# NV08C_GPS_shield_v1_1_reduced.net
KiCad netlist of a schematic drawn in EAGLE
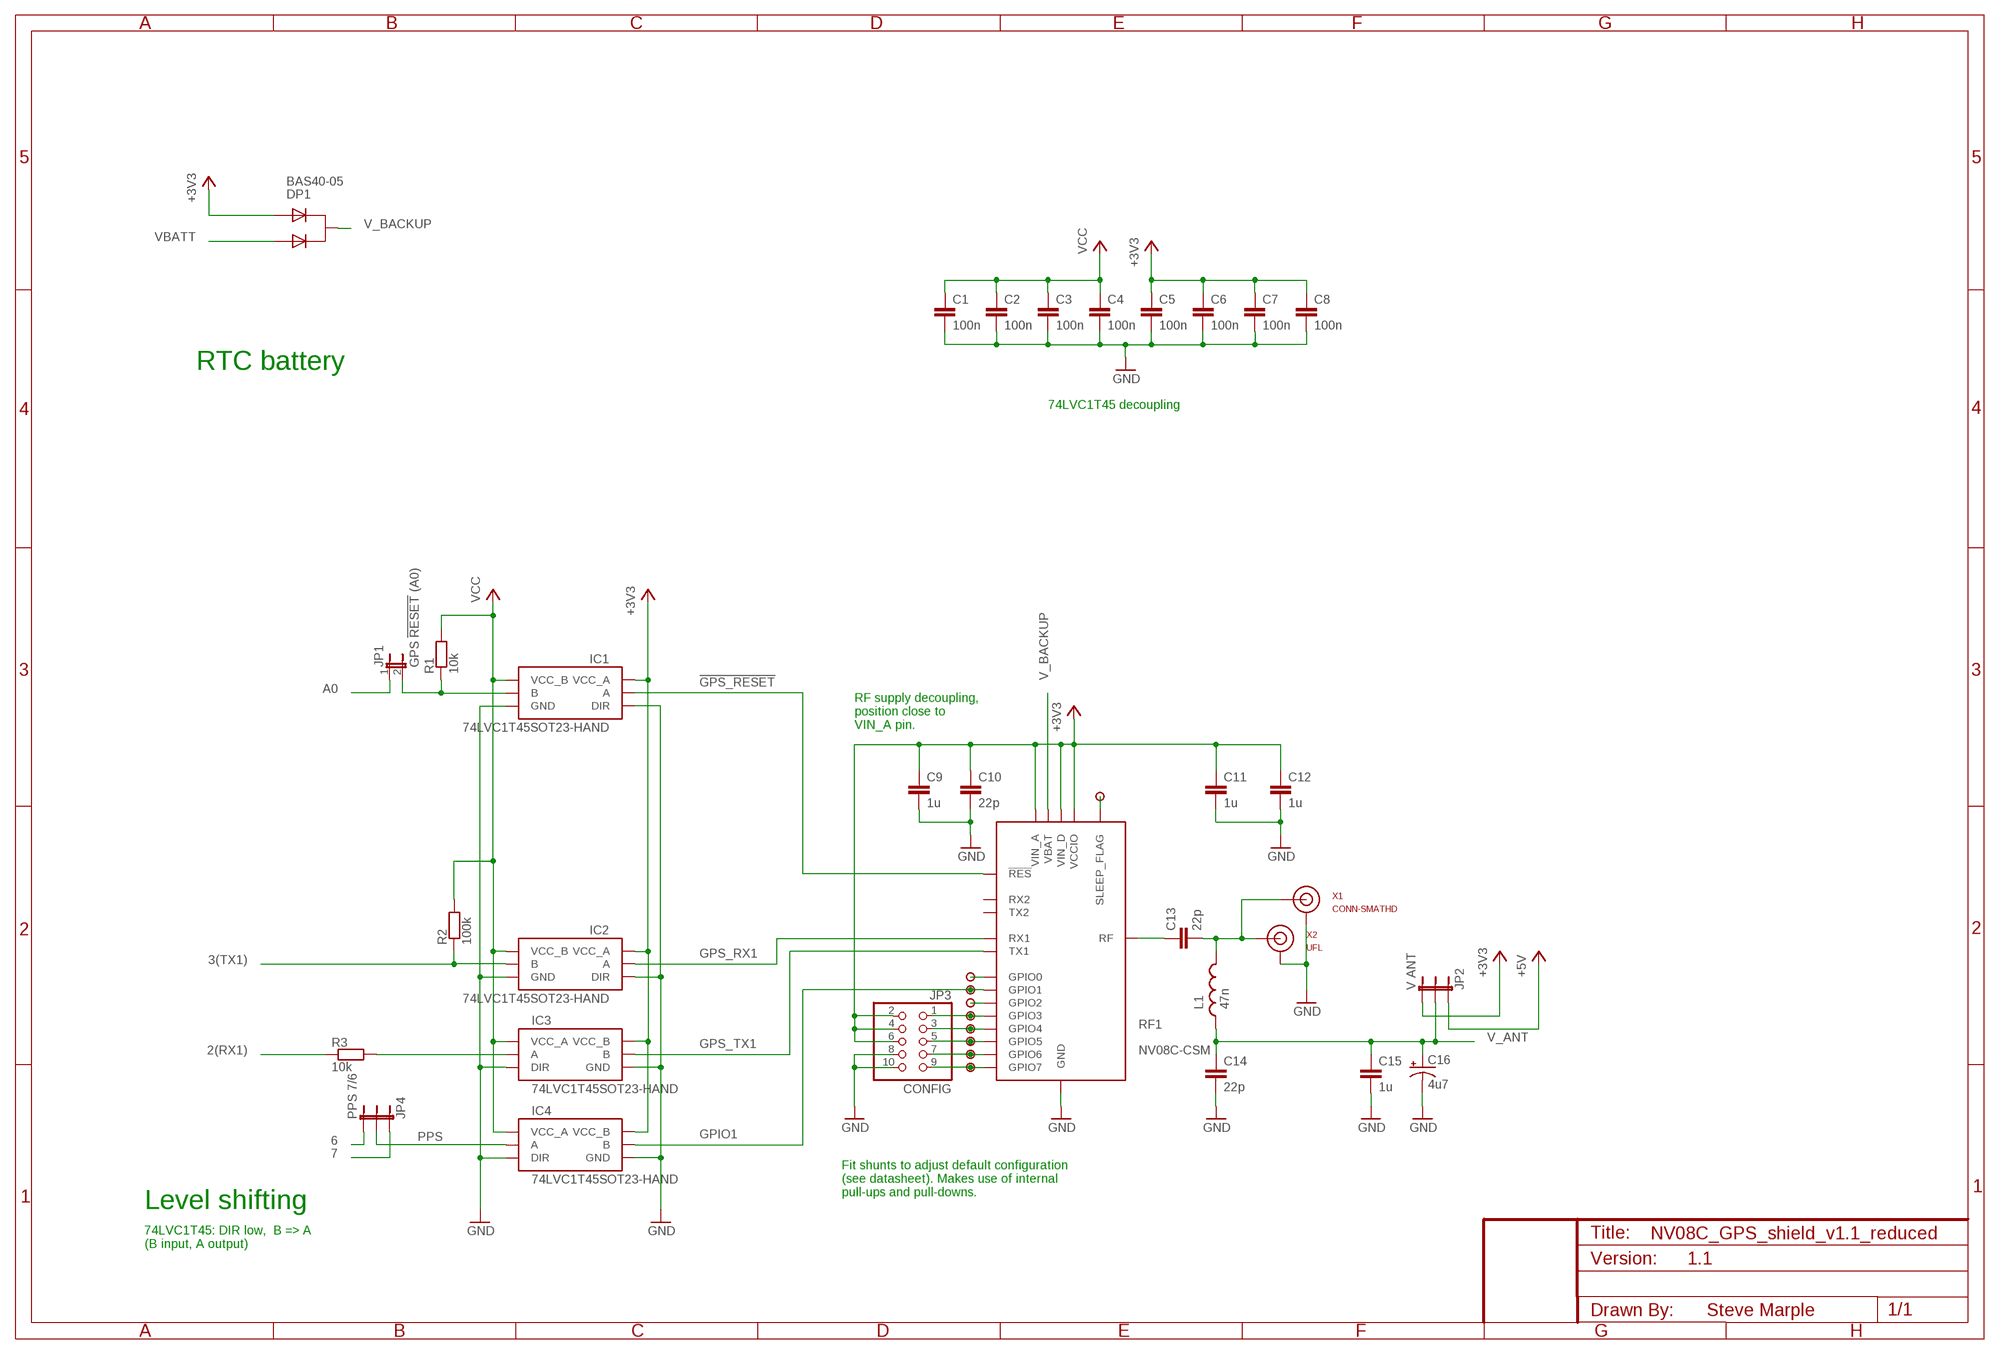
[diagram p0: schematic, sheet 1]

(export (version "E")
  (design (tool "Eeschema 10.0.6"))
  (components
    (comp (ref "C1")
      (value "100n")
      (footprint "eagle-import:1206-HAND")
      (libsource (lib "eagle-import") (part "C-EU1206-HAND"))
    )
    (comp (ref "C2")
      (value "100n")
      (footprint "eagle-import:1206-HAND")
      (libsource (lib "eagle-import") (part "C-EU1206-HAND"))
    )
    (comp (ref "C3")
      (value "100n")
      (footprint "eagle-import:1206-HAND")
      (libsource (lib "eagle-import") (part "C-EU1206-HAND"))
    )
    (comp (ref "C4")
      (value "100n")
      (footprint "eagle-import:1206-HAND")
      (libsource (lib "eagle-import") (part "C-EU1206-HAND"))
    )
    (comp (ref "C5")
      (value "100n")
      (footprint "eagle-import:1206-HAND")
      (libsource (lib "eagle-import") (part "C-EU1206-HAND"))
    )
    (comp (ref "C6")
      (value "100n")
      (footprint "eagle-import:1206-HAND")
      (libsource (lib "eagle-import") (part "C-EU1206-HAND"))
    )
    (comp (ref "C7")
      (value "100n")
      (footprint "eagle-import:1206-HAND")
      (libsource (lib "eagle-import") (part "C-EU1206-HAND"))
    )
    (comp (ref "C8")
      (value "100n")
      (footprint "eagle-import:1206-HAND")
      (libsource (lib "eagle-import") (part "C-EU1206-HAND"))
    )
    (comp (ref "C9")
      (value "1u")
      (footprint "eagle-import:1206-HAND")
      (libsource (lib "eagle-import") (part "C-EU1206-HAND"))
    )
    (comp (ref "C10")
      (value "22p")
      (footprint "eagle-import:0805-HAND")
      (libsource (lib "eagle-import") (part "C-EU0805-HAND"))
    )
    (comp (ref "C11")
      (value "1u")
      (footprint "eagle-import:1206-HAND")
      (libsource (lib "eagle-import") (part "C-EU1206-HAND"))
    )
    (comp (ref "C12")
      (value "1u")
      (footprint "eagle-import:1206-HAND")
      (libsource (lib "eagle-import") (part "C-EU1206-HAND"))
    )
    (comp (ref "C13")
      (value "22p")
      (footprint "eagle-import:0805-HAND")
      (libsource (lib "eagle-import") (part "C-EU0805-HAND"))
    )
    (comp (ref "C14")
      (value "22p")
      (footprint "eagle-import:0805-HAND")
      (libsource (lib "eagle-import") (part "C-EU0805-HAND"))
    )
    (comp (ref "C15")
      (value "1u")
      (footprint "eagle-import:1206-HAND")
      (libsource (lib "eagle-import") (part "C-EU1206-HAND"))
    )
    (comp (ref "C16")
      (value "4u7")
      (footprint "eagle-import:CPOL-RADIAL-10UF-25V")
      (libsource (lib "eagle-import") (part "CAP_POLPTH2"))
    )
    (comp (ref "DP1")
      (value "BAS40-05")
      (footprint "eagle-import:SOT23-3-HAND")
      (libsource (lib "eagle-import") (part "DIODE-PAIR-COMMON-CATHODE"))
    )
    (comp (ref "IC1")
      (value "74LVC1T45SOT23-HAND")
      (footprint "eagle-import:SOT23-6-HAND")
      (libsource (lib "eagle-import") (part "74LVC1T45SOT23-HAND"))
    )
    (comp (ref "IC2")
      (value "74LVC1T45SOT23-HAND")
      (footprint "eagle-import:SOT23-6-HAND")
      (libsource (lib "eagle-import") (part "74LVC1T45SOT23-HAND"))
    )
    (comp (ref "IC3")
      (value "74LVC1T45SOT23-HAND")
      (footprint "eagle-import:SOT23-6-HAND")
      (libsource (lib "eagle-import") (part "74LVC1T45SOT23-HAND"))
    )
    (comp (ref "IC4")
      (value "74LVC1T45SOT23-HAND")
      (footprint "eagle-import:SOT23-6-HAND")
      (libsource (lib "eagle-import") (part "74LVC1T45SOT23-HAND"))
    )
    (comp (ref "JP1")
      (value "GPS !RESET! (A0)")
      (footprint "eagle-import:1X02")
      (libsource (lib "eagle-import") (part "JUMPER-2PTH"))
    )
    (comp (ref "JP2")
      (value "V ANT")
      (footprint "eagle-import:1X03")
      (libsource (lib "eagle-import") (part "JUMPER-3PTH"))
    )
    (comp (ref "JP3")
      (value "CONFIG")
      (footprint "eagle-import:2X05")
      (libsource (lib "eagle-import") (part "PINHD-2X5"))
    )
    (comp (ref "JP4")
      (value "PPS 7/6")
      (footprint "eagle-import:1X03")
      (libsource (lib "eagle-import") (part "JUMPER-3PTH"))
    )
    (comp (ref "L1")
      (value "47n")
      (footprint "eagle-import:0805-HAND")
      (libsource (lib "eagle-import") (part "INDUCTOR0805-HAND"))
    )
    (comp (ref "R1")
      (value "10k")
      (footprint "eagle-import:1206-HAND")
      (libsource (lib "eagle-import") (part "RESISTOR1206-HAND"))
    )
    (comp (ref "R2")
      (value "100k")
      (footprint "eagle-import:1206-HAND")
      (libsource (lib "eagle-import") (part "RESISTOR1206-HAND"))
    )
    (comp (ref "R3")
      (value "10k")
      (footprint "eagle-import:1206-HAND")
      (libsource (lib "eagle-import") (part "RESISTOR1206-HAND"))
    )
    (comp (ref "RF1")
      (value "NV08C-CSM")
      (footprint "eagle-import:NVC08C-CSM-HAND")
      (libsource (lib "eagle-import") (part "NV08C-CSMHAND"))
    )
    (comp (ref "U$1")
      (value "PAD")
      (footprint "eagle-import:PAD")
      (libsource (lib "eagle-import") (part "PAD"))
    )
    (comp (ref "U$2")
      (value "PAD")
      (footprint "eagle-import:PAD")
      (libsource (lib "eagle-import") (part "PAD"))
    )
    (comp (ref "U$3")
      (value "PAD")
      (footprint "eagle-import:PAD")
      (libsource (lib "eagle-import") (part "PAD"))
    )
    (comp (ref "U$4")
      (value "?")
      (footprint "eagle-import:PAD")
      (libsource (lib "eagle-import") (part "PAD"))
    )
    (comp (ref "U$5")
      (value "PAD")
      (footprint "eagle-import:PAD")
      (libsource (lib "eagle-import") (part "PAD"))
    )
    (comp (ref "U$6")
      (value "PAD")
      (footprint "eagle-import:PAD")
      (libsource (lib "eagle-import") (part "PAD"))
    )
    (comp (ref "U$7")
      (value "PAD")
      (footprint "eagle-import:PAD")
      (libsource (lib "eagle-import") (part "PAD"))
    )
    (comp (ref "U$8")
      (value "PAD")
      (footprint "eagle-import:PAD")
      (libsource (lib "eagle-import") (part "PAD"))
    )
    (comp (ref "U$9")
      (value "PAD")
      (footprint "eagle-import:PAD")
      (libsource (lib "eagle-import") (part "PAD"))
    )
    (comp (ref "X1")
      (value "CONN-SMATHD")
      (footprint "eagle-import:SMA-THD")
      (libsource (lib "eagle-import") (part "CONN-SMATHD"))
    )
    (comp (ref "X2")
      (value "UFL")
      (footprint "eagle-import:CONN-UFL-HAND-SOLDERING")
      (libsource (lib "eagle-import") (part "CONN-UFLHAND"))
    )
  )
  (nets
    (net (code "1") (name "+3V3") (class "Default")
      (node (ref "C10") (pin "1") (pinfunction "1_1") (pintype "passive"))
      (node (ref "C11") (pin "1") (pinfunction "1_1") (pintype "passive"))
      (node (ref "C12") (pin "1") (pinfunction "1_1") (pintype "passive"))
      (node (ref "C5") (pin "1") (pinfunction "1_1") (pintype "passive"))
      (node (ref "C6") (pin "1") (pinfunction "1_1") (pintype "passive"))
      (node (ref "C7") (pin "1") (pinfunction "1_1") (pintype "passive"))
      (node (ref "C8") (pin "1") (pinfunction "1_1") (pintype "passive"))
      (node (ref "C9") (pin "1") (pinfunction "1_1") (pintype "passive"))
      (node (ref "DP1") (pin "2") (pinfunction "A2_2") (pintype "passive"))
      (node (ref "IC1") (pin "1") (pinfunction "VCC_A_1") (pintype "power_in"))
      (node (ref "IC2") (pin "1") (pinfunction "VCC_A_1") (pintype "power_in"))
      (node (ref "IC3") (pin "6") (pinfunction "VCC_B_6") (pintype "power_in"))
      (node (ref "IC4") (pin "6") (pinfunction "VCC_B_6") (pintype "power_in"))
      (node (ref "JP2") (pin "3") (pinfunction "3_3") (pintype "passive"))
      (node (ref "JP3") (pin "2") (pinfunction "2_2") (pintype "passive"))
      (node (ref "JP3") (pin "4") (pinfunction "4_4") (pintype "passive"))
      (node (ref "JP3") (pin "6") (pinfunction "6_6") (pintype "passive"))
      (node (ref "RF1") (pin "P$26") (pinfunction "VIN_D_P$26") (pintype "power_in"))
      (node (ref "RF1") (pin "P$28") (pinfunction "VCCIO_P$28") (pintype "power_in"))
      (node (ref "RF1") (pin "P$8") (pinfunction "VIN_A_P$8") (pintype "power_in"))
    )
    (net (code "2") (name "+5V") (class "Default")
      (node (ref "JP2") (pin "1") (pinfunction "1_1") (pintype "passive"))
    )
    (net (code "3") (name "/2(RX1)") (class "Default")
      (node (ref "R3") (pin "1") (pinfunction "1_1") (pintype "passive"))
    )
    (net (code "4") (name "/3(TX1)") (class "Default")
      (node (ref "IC2") (pin "4") (pinfunction "B_4") (pintype "bidirectional"))
      (node (ref "R2") (pin "1") (pinfunction "1_1") (pintype "passive"))
    )
    (net (code "5") (name "/6") (class "Default")
      (node (ref "JP4") (pin "3") (pinfunction "3_3") (pintype "passive"))
    )
    (net (code "6") (name "/7") (class "Default")
      (node (ref "JP4") (pin "1") (pinfunction "1_1") (pintype "passive"))
    )
    (net (code "7") (name "/A0") (class "Default")
      (node (ref "JP1") (pin "1") (pinfunction "1_1") (pintype "passive"))
    )
    (net (code "8") (name "/GPIO1") (class "Default")
      (node (ref "IC4") (pin "4") (pinfunction "B_4") (pintype "bidirectional"))
      (node (ref "RF1") (pin "P$2") (pinfunction "GPIO1_P$2") (pintype "bidirectional"))
      (node (ref "U$3") (pin "1") (pinfunction "1_1") (pintype "bidirectional"))
    )
    (net (code "9") (name "/GPS_RX1") (class "Default")
      (node (ref "IC2") (pin "3") (pinfunction "A_3") (pintype "bidirectional"))
      (node (ref "RF1") (pin "P$33") (pinfunction "RX1_P$33") (pintype "input"))
    )
    (net (code "10") (name "/GPS_TX1") (class "Default")
      (node (ref "IC3") (pin "4") (pinfunction "B_4") (pintype "bidirectional"))
      (node (ref "RF1") (pin "P$32") (pinfunction "TX1_P$32") (pintype "output"))
    )
    (net (code "11") (name "/PPS") (class "Default")
      (node (ref "IC4") (pin "3") (pinfunction "A_3") (pintype "bidirectional"))
      (node (ref "JP4") (pin "2") (pinfunction "2_2") (pintype "passive"))
    )
    (net (code "12") (name "/VBATT") (class "Default")
      (node (ref "DP1") (pin "1") (pinfunction "A1_1") (pintype "passive"))
    )
    (net (code "13") (name "/V_ANT") (class "Default")
      (node (ref "C14") (pin "1") (pinfunction "1_1") (pintype "passive"))
      (node (ref "C15") (pin "1") (pinfunction "1_1") (pintype "passive"))
      (node (ref "C16") (pin "1") (pinfunction "+_1") (pintype "passive"))
      (node (ref "JP2") (pin "2") (pinfunction "2_2") (pintype "passive"))
      (node (ref "L1") (pin "1") (pinfunction "1_1") (pintype "passive"))
    )
    (net (code "14") (name "/V_BACKUP") (class "Default")
      (node (ref "DP1") (pin "3") (pinfunction "C_3") (pintype "passive"))
      (node (ref "RF1") (pin "P$23") (pinfunction "VBAT_P$23") (pintype "power_in"))
    )
    (net (code "15") (name "/~{GPS_RESET}") (class "Default")
      (node (ref "IC1") (pin "3") (pinfunction "A_3") (pintype "bidirectional"))
      (node (ref "RF1") (pin "P$25") (pinfunction "~{RES}_P$25") (pintype "input"))
    )
    (net (code "16") (name "GND") (class "Default")
      (node (ref "C1") (pin "2") (pinfunction "2_2") (pintype "passive"))
      (node (ref "C10") (pin "2") (pinfunction "2_2") (pintype "passive"))
      (node (ref "C11") (pin "2") (pinfunction "2_2") (pintype "passive"))
      (node (ref "C12") (pin "2") (pinfunction "2_2") (pintype "passive"))
      (node (ref "C14") (pin "2") (pinfunction "2_2") (pintype "passive"))
      (node (ref "C15") (pin "2") (pinfunction "2_2") (pintype "passive"))
      (node (ref "C16") (pin "2") (pinfunction "-_2") (pintype "passive"))
      (node (ref "C2") (pin "2") (pinfunction "2_2") (pintype "passive"))
      (node (ref "C3") (pin "2") (pinfunction "2_2") (pintype "passive"))
      (node (ref "C4") (pin "2") (pinfunction "2_2") (pintype "passive"))
      (node (ref "C5") (pin "2") (pinfunction "2_2") (pintype "passive"))
      (node (ref "C6") (pin "2") (pinfunction "2_2") (pintype "passive"))
      (node (ref "C7") (pin "2") (pinfunction "2_2") (pintype "passive"))
      (node (ref "C8") (pin "2") (pinfunction "2_2") (pintype "passive"))
      (node (ref "C9") (pin "2") (pinfunction "2_2") (pintype "passive"))
      (node (ref "IC1") (pin "2") (pinfunction "GND_2") (pintype "power_in"))
      (node (ref "IC1") (pin "5") (pinfunction "DIR_5") (pintype "input"))
      (node (ref "IC2") (pin "2") (pinfunction "GND_2") (pintype "power_in"))
      (node (ref "IC2") (pin "5") (pinfunction "DIR_5") (pintype "input"))
      (node (ref "IC3") (pin "2") (pinfunction "GND_2") (pintype "power_in"))
      (node (ref "IC3") (pin "5") (pinfunction "DIR_5") (pintype "input"))
      (node (ref "IC4") (pin "2") (pinfunction "GND_2") (pintype "power_in"))
      (node (ref "IC4") (pin "5") (pinfunction "DIR_5") (pintype "input"))
      (node (ref "JP3") (pin "10") (pinfunction "10_10") (pintype "passive"))
      (node (ref "JP3") (pin "8") (pinfunction "8_8") (pintype "passive"))
      (node (ref "RF1") (pin "P$10") (pinfunction "GND_P$10") (pintype "power_in"))
      (node (ref "RF1") (pin "P$11") (pinfunction "GND_P$11") (pintype "power_in"))
      (node (ref "RF1") (pin "P$12") (pinfunction "GND_P$12") (pintype "power_in"))
      (node (ref "RF1") (pin "P$13") (pinfunction "GND_P$13") (pintype "power_in"))
      (node (ref "RF1") (pin "P$14") (pinfunction "GND_P$14") (pintype "power_in"))
      (node (ref "RF1") (pin "P$16") (pinfunction "GND_P$16") (pintype "power_in"))
      (node (ref "RF1") (pin "P$17") (pinfunction "GND_P$17") (pintype "power_in"))
      (node (ref "RF1") (pin "P$18") (pinfunction "GND_P$18") (pintype "power_in"))
      (node (ref "RF1") (pin "P$19") (pinfunction "GND_P$19") (pintype "power_in"))
      (node (ref "RF1") (pin "P$22") (pinfunction "GND_P$22") (pintype "power_in"))
      (node (ref "RF1") (pin "P$24") (pinfunction "GND_P$24") (pintype "power_in"))
      (node (ref "RF1") (pin "P$27") (pinfunction "GND_P$27") (pintype "power_in"))
      (node (ref "RF1") (pin "P$29") (pinfunction "GND_P$29") (pintype "power_in"))
      (node (ref "RF1") (pin "P$3") (pinfunction "GND_P$3") (pintype "power_in"))
      (node (ref "RF1") (pin "P$34") (pinfunction "GND_P$34") (pintype "power_in"))
      (node (ref "RF1") (pin "P$9") (pinfunction "GND_P$9") (pintype "power_in"))
      (node (ref "X1") (pin "GND@0") (pinfunction "GND_GND@0") (pintype "bidirectional"))
      (node (ref "X1") (pin "GND@1") (pinfunction "GND_GND@1") (pintype "bidirectional"))
      (node (ref "X1") (pin "GND@2") (pinfunction "GND_GND@2") (pintype "bidirectional"))
      (node (ref "X1") (pin "GND@3") (pinfunction "GND_GND@3") (pintype "bidirectional"))
      (node (ref "X2") (pin "GND@0") (pinfunction "GND_GND@0") (pintype "bidirectional"))
      (node (ref "X2") (pin "GND@1") (pinfunction "GND_GND@1") (pintype "bidirectional"))
    )
    (net (code "17") (name "Net-(IC1-B)") (class "Default")
      (node (ref "IC1") (pin "4") (pinfunction "B_4") (pintype "bidirectional"))
      (node (ref "JP1") (pin "2") (pinfunction "2_2") (pintype "passive"))
      (node (ref "R1") (pin "1") (pinfunction "1_1") (pintype "passive"))
    )
    (net (code "18") (name "Net-(IC3-A)") (class "Default")
      (node (ref "IC3") (pin "3") (pinfunction "A_3") (pintype "bidirectional"))
      (node (ref "R3") (pin "2") (pinfunction "2_2") (pintype "passive"))
    )
    (net (code "19") (name "Net-(RF1-GPIO0)") (class "Default")
      (node (ref "RF1") (pin "P$20") (pinfunction "GPIO0_P$20") (pintype "bidirectional"))
      (node (ref "U$2") (pin "1") (pinfunction "1_1") (pintype "bidirectional"))
    )
    (net (code "20") (name "Net-(RF1-GPIO2)") (class "Default")
      (node (ref "RF1") (pin "P$1") (pinfunction "GPIO2_P$1") (pintype "bidirectional"))
      (node (ref "U$4") (pin "1") (pinfunction "1_1") (pintype "bidirectional"))
    )
    (net (code "21") (name "Net-(RF1-GPIO3)") (class "Default")
      (node (ref "JP3") (pin "1") (pinfunction "1_1") (pintype "passive"))
      (node (ref "RF1") (pin "P$6") (pinfunction "GPIO3_P$6") (pintype "bidirectional"))
      (node (ref "U$5") (pin "1") (pinfunction "1_1") (pintype "bidirectional"))
    )
    (net (code "22") (name "Net-(RF1-GPIO4)") (class "Default")
      (node (ref "JP3") (pin "3") (pinfunction "3_3") (pintype "passive"))
      (node (ref "RF1") (pin "P$7") (pinfunction "GPIO4_P$7") (pintype "bidirectional"))
      (node (ref "U$6") (pin "1") (pinfunction "1_1") (pintype "bidirectional"))
    )
    (net (code "23") (name "Net-(RF1-GPIO5)") (class "Default")
      (node (ref "JP3") (pin "5") (pinfunction "5_5") (pintype "passive"))
      (node (ref "RF1") (pin "P$4") (pinfunction "GPIO5_P$4") (pintype "bidirectional"))
      (node (ref "U$7") (pin "1") (pinfunction "1_1") (pintype "bidirectional"))
    )
    (net (code "24") (name "Net-(RF1-GPIO6)") (class "Default")
      (node (ref "JP3") (pin "7") (pinfunction "7_7") (pintype "passive"))
      (node (ref "RF1") (pin "P$35") (pinfunction "GPIO6_P$35") (pintype "bidirectional"))
      (node (ref "U$8") (pin "1") (pinfunction "1_1") (pintype "bidirectional"))
    )
    (net (code "25") (name "Net-(RF1-GPIO7)") (class "Default")
      (node (ref "JP3") (pin "9") (pinfunction "9_9") (pintype "passive"))
      (node (ref "RF1") (pin "P$5") (pinfunction "GPIO7_P$5") (pintype "bidirectional"))
      (node (ref "U$9") (pin "1") (pinfunction "1_1") (pintype "bidirectional"))
    )
    (net (code "26") (name "Net-(RF1-RF)") (class "Default")
      (node (ref "C13") (pin "1") (pinfunction "1_1") (pintype "passive"))
      (node (ref "RF1") (pin "P$15") (pinfunction "RF_P$15") (pintype "input"))
    )
    (net (code "27") (name "Net-(RF1-SLEEP_FLAG)") (class "Default")
      (node (ref "RF1") (pin "P$21") (pinfunction "SLEEP_FLAG_P$21") (pintype "output"))
      (node (ref "U$1") (pin "1") (pinfunction "1_1") (pintype "bidirectional"))
    )
    (net (code "28") (name "Net-(X1-SIGNAL)") (class "Default")
      (node (ref "C13") (pin "2") (pinfunction "2_2") (pintype "passive"))
      (node (ref "L1") (pin "2") (pinfunction "2_2") (pintype "passive"))
      (node (ref "X1") (pin "SIG") (pinfunction "SIGNAL_SIG") (pintype "bidirectional"))
      (node (ref "X2") (pin "SIGNAL") (pinfunction "SIGNAL_SIGNAL") (pintype "bidirectional"))
    )
    (net (code "29") (name "VCC") (class "Default")
      (node (ref "C1") (pin "1") (pinfunction "1_1") (pintype "passive"))
      (node (ref "C2") (pin "1") (pinfunction "1_1") (pintype "passive"))
      (node (ref "C3") (pin "1") (pinfunction "1_1") (pintype "passive"))
      (node (ref "C4") (pin "1") (pinfunction "1_1") (pintype "passive"))
      (node (ref "IC1") (pin "6") (pinfunction "VCC_B_6") (pintype "power_in"))
      (node (ref "IC2") (pin "6") (pinfunction "VCC_B_6") (pintype "power_in"))
      (node (ref "IC3") (pin "1") (pinfunction "VCC_A_1") (pintype "power_in"))
      (node (ref "IC4") (pin "1") (pinfunction "VCC_A_1") (pintype "power_in"))
      (node (ref "R1") (pin "2") (pinfunction "2_2") (pintype "passive"))
      (node (ref "R2") (pin "2") (pinfunction "2_2") (pintype "passive"))
    )
    (net (code "30") (name "unconnected-(RF1-RX2-PadP$30)") (class "Default")
      (node (ref "RF1") (pin "P$30") (pinfunction "RX2_P$30") (pintype "input"))
    )
    (net (code "31") (name "unconnected-(RF1-TX2-PadP$31)") (class "Default")
      (node (ref "RF1") (pin "P$31") (pinfunction "TX2_P$31") (pintype "output"))
    )
  )
)
